# 1_P1_schdoc.net
KiCad netlist of a schematic drawn in Altium Designer
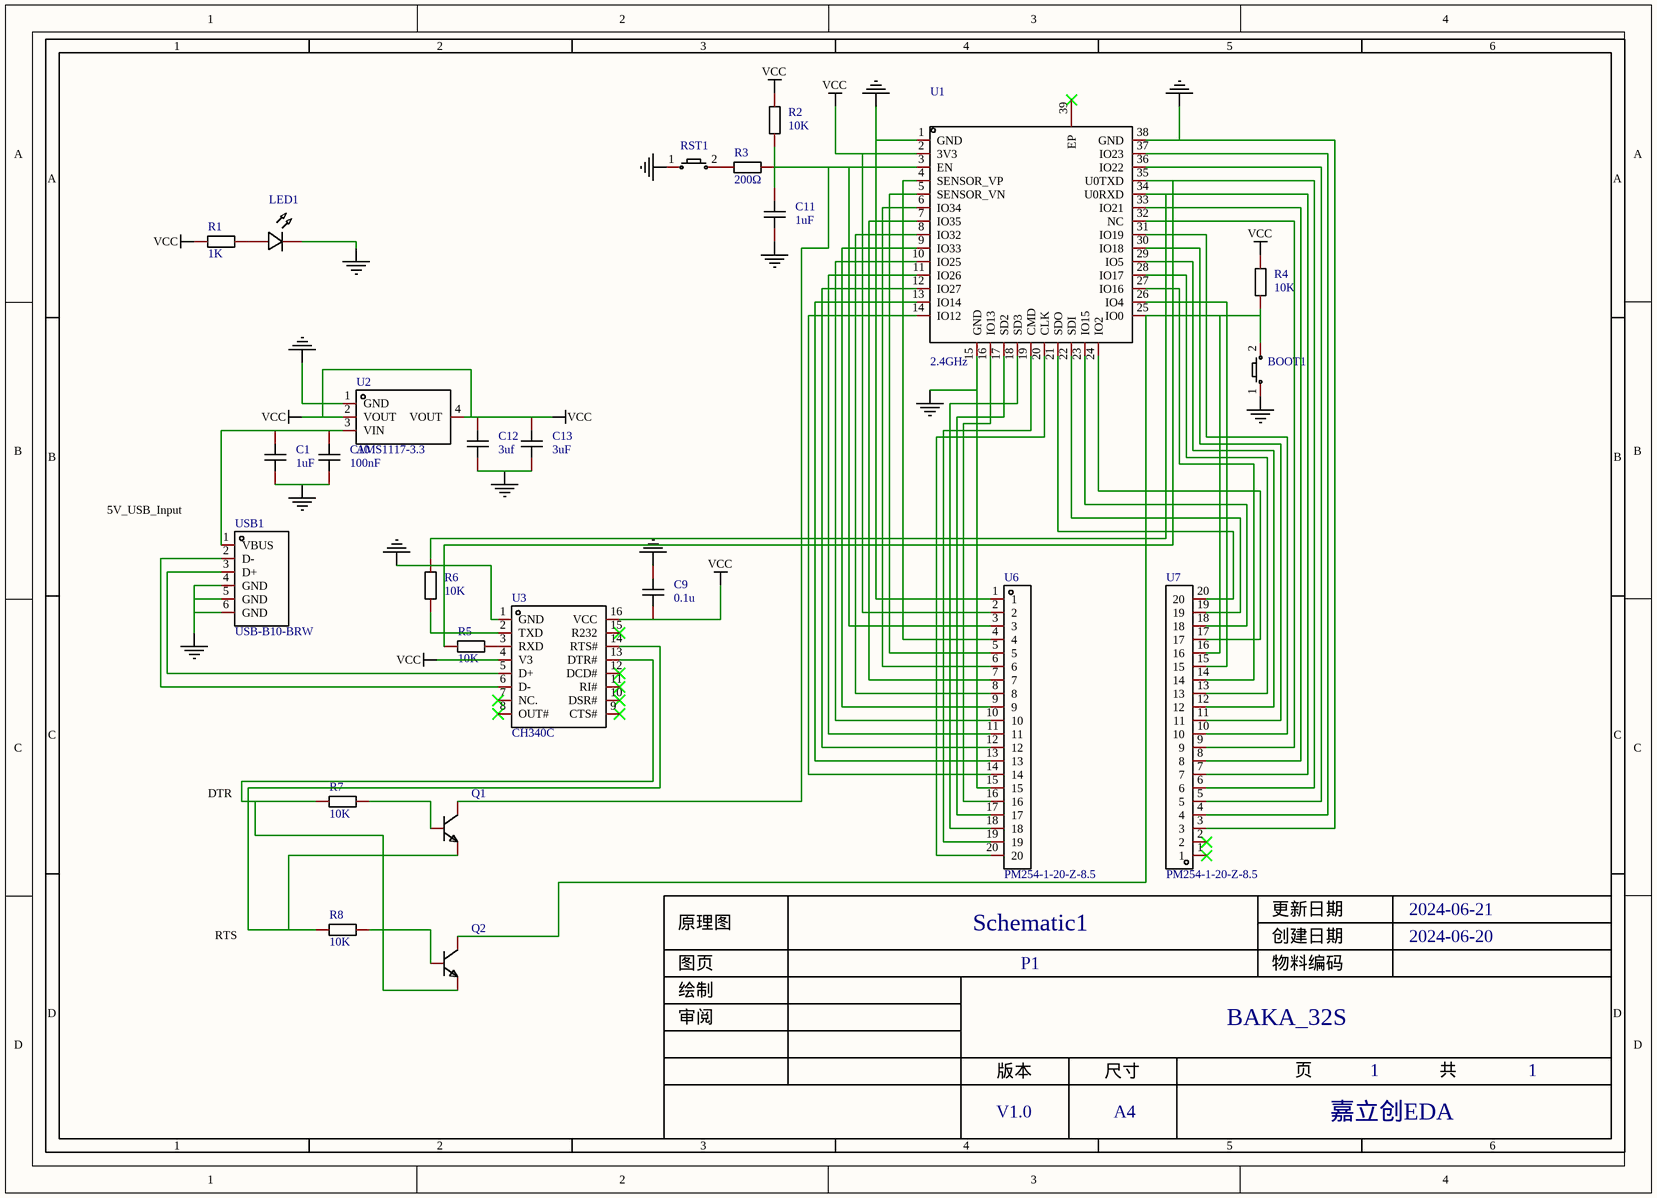
[diagram p0: 1_P1.schdoc.schdoc]

(export (version "E")
  (design (tool "Eeschema 10.0.6"))
  (components
    (comp (ref "BOOT1")
      (value "Key_SMD_3x4x2")
      (libsource (lib "altium-import") (part "root_1_Key_SMD_3x4x2_"))
    )
    (comp (ref "C1")
      (value "1uF")
      (fields (field (name "NAME") "1uF"))
      (libsource (lib "altium-import") (part "root_1_CAP_0603_"))
    )
    (comp (ref "C9")
      (value "0.1u")
      (fields (field (name "NAME") "0.1u"))
      (libsource (lib "altium-import") (part "root_1_CAP_0603_"))
    )
    (comp (ref "C10")
      (value "100nF")
      (fields (field (name "NAME") "100nF"))
      (libsource (lib "altium-import") (part "root_1_CAP_0603_"))
    )
    (comp (ref "C11")
      (value "1uF")
      (fields (field (name "NAME") "1uF"))
      (libsource (lib "altium-import") (part "root_1_CAP_0603_"))
    )
    (comp (ref "C12")
      (value "3uf")
      (fields (field (name "NAME") "3uf"))
      (libsource (lib "altium-import") (part "root_1_CAP_0603_"))
    )
    (comp (ref "C13")
      (value "3uF")
      (fields (field (name "NAME") "3uF"))
      (libsource (lib "altium-import") (part "root_1_CAP_0603_"))
    )
    (comp (ref "LED1") (value "LED_0603-R") (libsource (lib "altium-import") (part "root_0_LED_0603-R_")))
    (comp (ref "Q1") (value "S8050_SOT_NPN") (libsource (lib "altium-import") (part "root_0_S8050_SOT_NPN_")))
    (comp (ref "Q2") (value "S8050_SOT_NPN") (libsource (lib "altium-import") (part "root_0_S8050_SOT_NPN_")))
    (comp (ref "R1")
      (value "1K")
      (fields (field (name "NAME") "1K"))
      (libsource (lib "altium-import") (part "root_0_Res_0603_"))
    )
    (comp (ref "R2")
      (value "10K")
      (fields (field (name "NAME") "10K"))
      (libsource (lib "altium-import") (part "root_1_Res_0603_"))
    )
    (comp (ref "R3")
      (value "200Ω")
      (fields (field (name "NAME") "200Ω"))
      (libsource (lib "altium-import") (part "root_0_Res_0603_"))
    )
    (comp (ref "R4")
      (value "10K")
      (fields (field (name "NAME") "10K"))
      (libsource (lib "altium-import") (part "root_1_Res_0603_"))
    )
    (comp (ref "R5")
      (value "10K")
      (fields (field (name "NAME") "10K"))
      (libsource (lib "altium-import") (part "root_0_Res_0603_"))
    )
    (comp (ref "R6")
      (value "10K")
      (fields (field (name "NAME") "10K"))
      (libsource (lib "altium-import") (part "root_1_Res_0603_"))
    )
    (comp (ref "R7")
      (value "10K")
      (fields (field (name "NAME") "10K"))
      (libsource (lib "altium-import") (part "root_0_Res_0603_"))
    )
    (comp (ref "R8")
      (value "10K")
      (fields (field (name "NAME") "10K"))
      (libsource (lib "altium-import") (part "root_0_Res_0603_"))
    )
    (comp (ref "RST1")
      (value "Key_SMD_3x4x2")
      (libsource (lib "altium-import") (part "root_0_Key_SMD_3x4x2_"))
    )
    (comp (ref "U1")
      (value "2.4GHz")
      (description "核心处理器:ESP32芯片;频率:2.4GHz;天线形式:IPEX接口;发射功率:17dBm;接收灵敏度:-90dBm;")
      (fields
        (field (name "NAME") "2.4GHz")
        (field (name "MANUFACTURER") "Ai-Thinker(安信可)")
        (field (name "MANUFACTURER PART") "ESP32-S")
      )
      (libsource (lib "altium-import") (part "root_0_ESP32-S_"))
    )
    (comp (ref "U2")
      (value "AMS1117-3.3")
      (description "输出类型:固定;最大输入电压:-;输出电压:3.3V;最大输出电流:1A;电源纹波抑制比(PSRR):72dB@(120Hz);输出极性:正极;")
      (fields (field (name "NAME") "AMS1117-3.3") (field (name "MANUFACTURER") "AMS"))
      (libsource (lib "altium-import") (part "root_0_AMS1117-3.3_C6186_"))
    )
    (comp (ref "U3")
      (value "CH340C")
      (description "应用功能:收发器;接口协议:USB 2.0;数据速率:2Mbps;")
      (fields (field (name "NAME") "CH340C") (field (name "MANUFACTURER") "WCH(南京沁恒)"))
      (libsource (lib "altium-import") (part "root_0_CH340C_"))
    )
    (comp (ref "U6")
      (value "PM254-1-20-Z-8.5")
      (fields (field (name "NAME") "PM254-1-20-Z-8.5") (field (name "MANUFACTURER") "HCTL(华灿天禄)"))
      (libsource (lib "altium-import") (part "root_0_PM254-1-20-Z-8.5_"))
    )
    (comp (ref "U7")
      (value "PM254-1-20-Z-8.5")
      (fields (field (name "NAME") "PM254-1-20-Z-8.5") (field (name "MANUFACTURER") "HCTL(华灿天禄)"))
      (libsource (lib "altium-import") (part "root_2_PM254-1-20-Z-8.5_"))
    )
    (comp (ref "USB1")
      (value "USB-B10-BRW")
      (fields (field (name "NAME") "USB-B10-BRW") (field (name "MANUFACTURER") "XUNPU(讯普)"))
      (libsource (lib "altium-import") (part "root_0_USB-B10-BRW_"))
    )
  )
  (nets
    (net (code "1") (name "GND") (class "Default")
      (node (ref "BOOT1") (pin "1") (pinfunction "1_1") (pintype "passive"))
      (node (ref "C1") (pin "1") (pinfunction "1_1") (pintype "passive"))
      (node (ref "C10") (pin "1") (pinfunction "1_1") (pintype "passive"))
      (node (ref "C11") (pin "1") (pinfunction "1_1") (pintype "passive"))
      (node (ref "C12") (pin "1") (pinfunction "1_1") (pintype "passive"))
      (node (ref "C13") (pin "1") (pinfunction "1_1") (pintype "passive"))
      (node (ref "C9") (pin "2") (pinfunction "2_2") (pintype "passive"))
      (node (ref "LED1") (pin "1") (pinfunction "C_1") (pintype "passive"))
      (node (ref "RST1") (pin "1") (pinfunction "1_1") (pintype "passive"))
      (node (ref "U1") (pin "1") (pinfunction "GND_1") (pintype "passive"))
      (node (ref "U1") (pin "15") (pinfunction "GND_15") (pintype "passive"))
      (node (ref "U1") (pin "38") (pinfunction "GND_38") (pintype "passive"))
      (node (ref "U2") (pin "1") (pinfunction "GND_1") (pintype "passive"))
      (node (ref "U3") (pin "1") (pinfunction "GND_1") (pintype "passive"))
      (node (ref "U6") (pin "1") (pinfunction "1_1") (pintype "passive"))
      (node (ref "U6") (pin "15") (pinfunction "15_15") (pintype "passive"))
      (node (ref "U7") (pin "3") (pinfunction "3_3") (pintype "passive"))
      (node (ref "USB1") (pin "4") (pinfunction "GND_4") (pintype "passive"))
      (node (ref "USB1") (pin "5") (pinfunction "GND_5") (pintype "passive"))
      (node (ref "USB1") (pin "6") (pinfunction "GND_6") (pintype "passive"))
    )
    (net (code "2") (name "Net-(LED1-A)") (class "Default")
      (node (ref "LED1") (pin "2") (pinfunction "A_2") (pintype "passive"))
      (node (ref "R1") (pin "2") (pinfunction "2_2") (pintype "passive"))
    )
    (net (code "3") (name "Net-(Q1-Pad1)") (class "Default")
      (node (ref "Q1") (pin "1") (pinfunction "1_1") (pintype "passive"))
      (node (ref "R7") (pin "2") (pinfunction "2_2") (pintype "passive"))
    )
    (net (code "4") (name "Net-(Q2-Pad1)") (class "Default")
      (node (ref "Q2") (pin "1") (pinfunction "1_1") (pintype "passive"))
      (node (ref "R8") (pin "2") (pinfunction "2_2") (pintype "passive"))
    )
    (net (code "5") (name "Net-(R3-Pad1)") (class "Default")
      (node (ref "R3") (pin "1") (pinfunction "1_1") (pintype "passive"))
      (node (ref "RST1") (pin "2") (pinfunction "2_2") (pintype "passive"))
    )
    (net (code "6") (name "Net-(U1-CLK)") (class "Default")
      (node (ref "U1") (pin "20") (pinfunction "CLK_20") (pintype "passive"))
      (node (ref "U6") (pin "20") (pinfunction "20_20") (pintype "passive"))
    )
    (net (code "7") (name "Net-(U1-CMD)") (class "Default")
      (node (ref "U1") (pin "19") (pinfunction "CMD_19") (pintype "passive"))
      (node (ref "U6") (pin "19") (pinfunction "19_19") (pintype "passive"))
    )
    (net (code "8") (name "Net-(U1-EN)") (class "Default")
      (node (ref "C11") (pin "2") (pinfunction "2_2") (pintype "passive"))
      (node (ref "Q1") (pin "3") (pinfunction "3_3") (pintype "passive"))
      (node (ref "R2") (pin "1") (pinfunction "1_1") (pintype "passive"))
      (node (ref "R3") (pin "2") (pinfunction "2_2") (pintype "passive"))
      (node (ref "U1") (pin "3") (pinfunction "EN_3") (pintype "passive"))
      (node (ref "U6") (pin "3") (pinfunction "3_3") (pintype "passive"))
    )
    (net (code "9") (name "Net-(U1-IO0)") (class "Default")
      (node (ref "BOOT1") (pin "2") (pinfunction "2_2") (pintype "passive"))
      (node (ref "Q2") (pin "3") (pinfunction "3_3") (pintype "passive"))
      (node (ref "R4") (pin "1") (pinfunction "1_1") (pintype "passive"))
      (node (ref "U1") (pin "25") (pinfunction "IO0_25") (pintype "passive"))
      (node (ref "U7") (pin "16") (pinfunction "16_16") (pintype "passive"))
    )
    (net (code "10") (name "Net-(U1-IO2)") (class "Default")
      (node (ref "U1") (pin "24") (pinfunction "IO2_24") (pintype "passive"))
      (node (ref "U7") (pin "17") (pinfunction "17_17") (pintype "passive"))
    )
    (net (code "11") (name "Net-(U1-IO4)") (class "Default")
      (node (ref "U1") (pin "26") (pinfunction "IO4_26") (pintype "passive"))
      (node (ref "U7") (pin "15") (pinfunction "15_15") (pintype "passive"))
    )
    (net (code "12") (name "Net-(U1-IO5)") (class "Default")
      (node (ref "U1") (pin "29") (pinfunction "IO5_29") (pintype "passive"))
      (node (ref "U7") (pin "12") (pinfunction "12_12") (pintype "passive"))
    )
    (net (code "13") (name "Net-(U1-IO12)") (class "Default")
      (node (ref "U1") (pin "14") (pinfunction "IO12_14") (pintype "passive"))
      (node (ref "U6") (pin "14") (pinfunction "14_14") (pintype "passive"))
    )
    (net (code "14") (name "Net-(U1-IO13)") (class "Default")
      (node (ref "U1") (pin "16") (pinfunction "IO13_16") (pintype "passive"))
      (node (ref "U6") (pin "16") (pinfunction "16_16") (pintype "passive"))
    )
    (net (code "15") (name "Net-(U1-IO14)") (class "Default")
      (node (ref "U1") (pin "13") (pinfunction "IO14_13") (pintype "passive"))
      (node (ref "U6") (pin "13") (pinfunction "13_13") (pintype "passive"))
    )
    (net (code "16") (name "Net-(U1-IO15)") (class "Default")
      (node (ref "U1") (pin "23") (pinfunction "IO15_23") (pintype "passive"))
      (node (ref "U7") (pin "18") (pinfunction "18_18") (pintype "passive"))
    )
    (net (code "17") (name "Net-(U1-IO16)") (class "Default")
      (node (ref "U1") (pin "27") (pinfunction "IO16_27") (pintype "passive"))
      (node (ref "U7") (pin "14") (pinfunction "14_14") (pintype "passive"))
    )
    (net (code "18") (name "Net-(U1-IO17)") (class "Default")
      (node (ref "U1") (pin "28") (pinfunction "IO17_28") (pintype "passive"))
      (node (ref "U7") (pin "13") (pinfunction "13_13") (pintype "passive"))
    )
    (net (code "19") (name "Net-(U1-IO18)") (class "Default")
      (node (ref "U1") (pin "30") (pinfunction "IO18_30") (pintype "passive"))
      (node (ref "U7") (pin "11") (pinfunction "11_11") (pintype "passive"))
    )
    (net (code "20") (name "Net-(U1-IO19)") (class "Default")
      (node (ref "U1") (pin "31") (pinfunction "IO19_31") (pintype "passive"))
      (node (ref "U7") (pin "10") (pinfunction "10_10") (pintype "passive"))
    )
    (net (code "21") (name "Net-(U1-IO21)") (class "Default")
      (node (ref "U1") (pin "33") (pinfunction "IO21_33") (pintype "passive"))
      (node (ref "U7") (pin "8") (pinfunction "8_8") (pintype "passive"))
    )
    (net (code "22") (name "Net-(U1-IO22)") (class "Default")
      (node (ref "U1") (pin "36") (pinfunction "IO22_36") (pintype "passive"))
      (node (ref "U7") (pin "5") (pinfunction "5_5") (pintype "passive"))
    )
    (net (code "23") (name "Net-(U1-IO23)") (class "Default")
      (node (ref "U1") (pin "37") (pinfunction "IO23_37") (pintype "passive"))
      (node (ref "U7") (pin "4") (pinfunction "4_4") (pintype "passive"))
    )
    (net (code "24") (name "Net-(U1-IO25)") (class "Default")
      (node (ref "U1") (pin "10") (pinfunction "IO25_10") (pintype "passive"))
      (node (ref "U6") (pin "10") (pinfunction "10_10") (pintype "passive"))
    )
    (net (code "25") (name "Net-(U1-IO26)") (class "Default")
      (node (ref "U1") (pin "11") (pinfunction "IO26_11") (pintype "passive"))
      (node (ref "U6") (pin "11") (pinfunction "11_11") (pintype "passive"))
    )
    (net (code "26") (name "Net-(U1-IO27)") (class "Default")
      (node (ref "U1") (pin "12") (pinfunction "IO27_12") (pintype "passive"))
      (node (ref "U6") (pin "12") (pinfunction "12_12") (pintype "passive"))
    )
    (net (code "27") (name "Net-(U1-IO32)") (class "Default")
      (node (ref "U1") (pin "8") (pinfunction "IO32_8") (pintype "passive"))
      (node (ref "U6") (pin "8") (pinfunction "8_8") (pintype "passive"))
    )
    (net (code "28") (name "Net-(U1-IO33)") (class "Default")
      (node (ref "U1") (pin "9") (pinfunction "IO33_9") (pintype "passive"))
      (node (ref "U6") (pin "9") (pinfunction "9_9") (pintype "passive"))
    )
    (net (code "29") (name "Net-(U1-IO34)") (class "Default")
      (node (ref "U1") (pin "6") (pinfunction "IO34_6") (pintype "passive"))
      (node (ref "U6") (pin "6") (pinfunction "6_6") (pintype "passive"))
    )
    (net (code "30") (name "Net-(U1-IO35)") (class "Default")
      (node (ref "U1") (pin "7") (pinfunction "IO35_7") (pintype "passive"))
      (node (ref "U6") (pin "7") (pinfunction "7_7") (pintype "passive"))
    )
    (net (code "31") (name "Net-(U1-NC)") (class "Default")
      (node (ref "U1") (pin "32") (pinfunction "NC_32") (pintype "passive"))
      (node (ref "U7") (pin "9") (pinfunction "9_9") (pintype "passive"))
    )
    (net (code "32") (name "Net-(U1-SD2)") (class "Default")
      (node (ref "U1") (pin "17") (pinfunction "SD2_17") (pintype "passive"))
      (node (ref "U6") (pin "17") (pinfunction "17_17") (pintype "passive"))
    )
    (net (code "33") (name "Net-(U1-SD3)") (class "Default")
      (node (ref "U1") (pin "18") (pinfunction "SD3_18") (pintype "passive"))
      (node (ref "U6") (pin "18") (pinfunction "18_18") (pintype "passive"))
    )
    (net (code "34") (name "Net-(U1-SDI)") (class "Default")
      (node (ref "U1") (pin "22") (pinfunction "SDI_22") (pintype "passive"))
      (node (ref "U7") (pin "19") (pinfunction "19_19") (pintype "passive"))
    )
    (net (code "35") (name "Net-(U1-SDO)") (class "Default")
      (node (ref "U1") (pin "21") (pinfunction "SDO_21") (pintype "passive"))
      (node (ref "U7") (pin "20") (pinfunction "20_20") (pintype "passive"))
    )
    (net (code "36") (name "Net-(U1-SENSOR_VN)") (class "Default")
      (node (ref "U1") (pin "5") (pinfunction "SENSOR_VN_5") (pintype "passive"))
      (node (ref "U6") (pin "5") (pinfunction "5_5") (pintype "passive"))
    )
    (net (code "37") (name "Net-(U1-SENSOR_VP)") (class "Default")
      (node (ref "U1") (pin "4") (pinfunction "SENSOR_VP_4") (pintype "passive"))
      (node (ref "U6") (pin "4") (pinfunction "4_4") (pintype "passive"))
    )
    (net (code "38") (name "Net-(U1-U0RXD)") (class "Default")
      (node (ref "R6") (pin "2") (pinfunction "2_2") (pintype "passive"))
      (node (ref "U1") (pin "34") (pinfunction "U0RXD_34") (pintype "passive"))
      (node (ref "U7") (pin "7") (pinfunction "7_7") (pintype "passive"))
    )
    (net (code "39") (name "Net-(U1-U0TXD)") (class "Default")
      (node (ref "R5") (pin "1") (pinfunction "1_1") (pintype "passive"))
      (node (ref "U1") (pin "35") (pinfunction "U0TXD_35") (pintype "passive"))
      (node (ref "U7") (pin "6") (pinfunction "6_6") (pintype "passive"))
    )
    (net (code "40") (name "Net-(U2-VIN)") (class "Default")
      (node (ref "C1") (pin "2") (pinfunction "2_2") (pintype "passive"))
      (node (ref "C10") (pin "2") (pinfunction "2_2") (pintype "passive"))
      (node (ref "U2") (pin "3") (pinfunction "VIN_3") (pintype "passive"))
      (node (ref "USB1") (pin "1") (pinfunction "VBUS_1") (pintype "passive"))
    )
    (net (code "41") (name "Net-(U3-D+)") (class "Default")
      (node (ref "U3") (pin "5") (pinfunction "D+_5") (pintype "passive"))
      (node (ref "USB1") (pin "3") (pinfunction "D+_3") (pintype "passive"))
    )
    (net (code "42") (name "Net-(U3-D-)") (class "Default")
      (node (ref "U3") (pin "6") (pinfunction "D-_6") (pintype "passive"))
      (node (ref "USB1") (pin "2") (pinfunction "D-_2") (pintype "passive"))
    )
    (net (code "43") (name "Net-(U3-DTR#)") (class "Default")
      (node (ref "Q2") (pin "2") (pinfunction "2_2") (pintype "passive"))
      (node (ref "R7") (pin "1") (pinfunction "1_1") (pintype "passive"))
      (node (ref "U3") (pin "13") (pinfunction "DTR#_13") (pintype "passive"))
    )
    (net (code "44") (name "Net-(U3-RTS#)") (class "Default")
      (node (ref "Q1") (pin "2") (pinfunction "2_2") (pintype "passive"))
      (node (ref "R8") (pin "1") (pinfunction "1_1") (pintype "passive"))
      (node (ref "U3") (pin "14") (pinfunction "RTS#_14") (pintype "passive"))
    )
    (net (code "45") (name "Net-(U3-RXD)") (class "Default")
      (node (ref "R5") (pin "2") (pinfunction "2_2") (pintype "passive"))
      (node (ref "U3") (pin "3") (pinfunction "RXD_3") (pintype "passive"))
    )
    (net (code "46") (name "Net-(U3-TXD)") (class "Default")
      (node (ref "R6") (pin "1") (pinfunction "1_1") (pintype "passive"))
      (node (ref "U3") (pin "2") (pinfunction "TXD_2") (pintype "passive"))
    )
    (net (code "47") (name "VCC") (class "Default")
      (node (ref "C12") (pin "2") (pinfunction "2_2") (pintype "passive"))
      (node (ref "C13") (pin "2") (pinfunction "2_2") (pintype "passive"))
      (node (ref "C9") (pin "1") (pinfunction "1_1") (pintype "passive"))
      (node (ref "R1") (pin "1") (pinfunction "1_1") (pintype "passive"))
      (node (ref "R2") (pin "2") (pinfunction "2_2") (pintype "passive"))
      (node (ref "R4") (pin "2") (pinfunction "2_2") (pintype "passive"))
      (node (ref "U1") (pin "2") (pinfunction "3V3_2") (pintype "passive"))
      (node (ref "U2") (pin "2") (pinfunction "VOUT_2") (pintype "passive"))
      (node (ref "U2") (pin "4") (pinfunction "VOUT_4") (pintype "passive"))
      (node (ref "U3") (pin "16") (pinfunction "VCC_16") (pintype "passive"))
      (node (ref "U3") (pin "4") (pinfunction "V3_4") (pintype "passive"))
      (node (ref "U6") (pin "2") (pinfunction "2_2") (pintype "passive"))
    )
    (net (code "48") (name "unconnected-(U1-EP-Pad39)") (class "Default")
      (node (ref "U1") (pin "39") (pinfunction "EP_39") (pintype "passive+no_connect"))
    )
    (net (code "49") (name "unconnected-(U3-CTS#-Pad9)") (class "Default")
      (node (ref "U3") (pin "9") (pinfunction "CTS#_9") (pintype "passive+no_connect"))
    )
    (net (code "50") (name "unconnected-(U3-DCD#-Pad12)") (class "Default")
      (node (ref "U3") (pin "12") (pinfunction "DCD#_12") (pintype "passive+no_connect"))
    )
    (net (code "51") (name "unconnected-(U3-DSR#-Pad10)") (class "Default")
      (node (ref "U3") (pin "10") (pinfunction "DSR#_10") (pintype "passive+no_connect"))
    )
    (net (code "52") (name "unconnected-(U3-NC.-Pad7)") (class "Default")
      (node (ref "U3") (pin "7") (pinfunction "NC._7") (pintype "passive+no_connect"))
    )
    (net (code "53") (name "unconnected-(U3-OUT#-Pad8)") (class "Default")
      (node (ref "U3") (pin "8") (pinfunction "OUT#_8") (pintype "passive+no_connect"))
    )
    (net (code "54") (name "unconnected-(U3-R232-Pad15)") (class "Default")
      (node (ref "U3") (pin "15") (pinfunction "R232_15") (pintype "passive+no_connect"))
    )
    (net (code "55") (name "unconnected-(U3-RI#-Pad11)") (class "Default")
      (node (ref "U3") (pin "11") (pinfunction "RI#_11") (pintype "passive+no_connect"))
    )
    (net (code "56") (name "unconnected-(U7-Pad1)") (class "Default")
      (node (ref "U7") (pin "1") (pinfunction "1_1") (pintype "passive+no_connect"))
    )
    (net (code "57") (name "unconnected-(U7-Pad2)") (class "Default")
      (node (ref "U7") (pin "2") (pinfunction "2_2") (pintype "passive+no_connect"))
    )
  )
)
